# Whastbee-display3.net
KiCad netlist of a schematic drawn in EAGLE
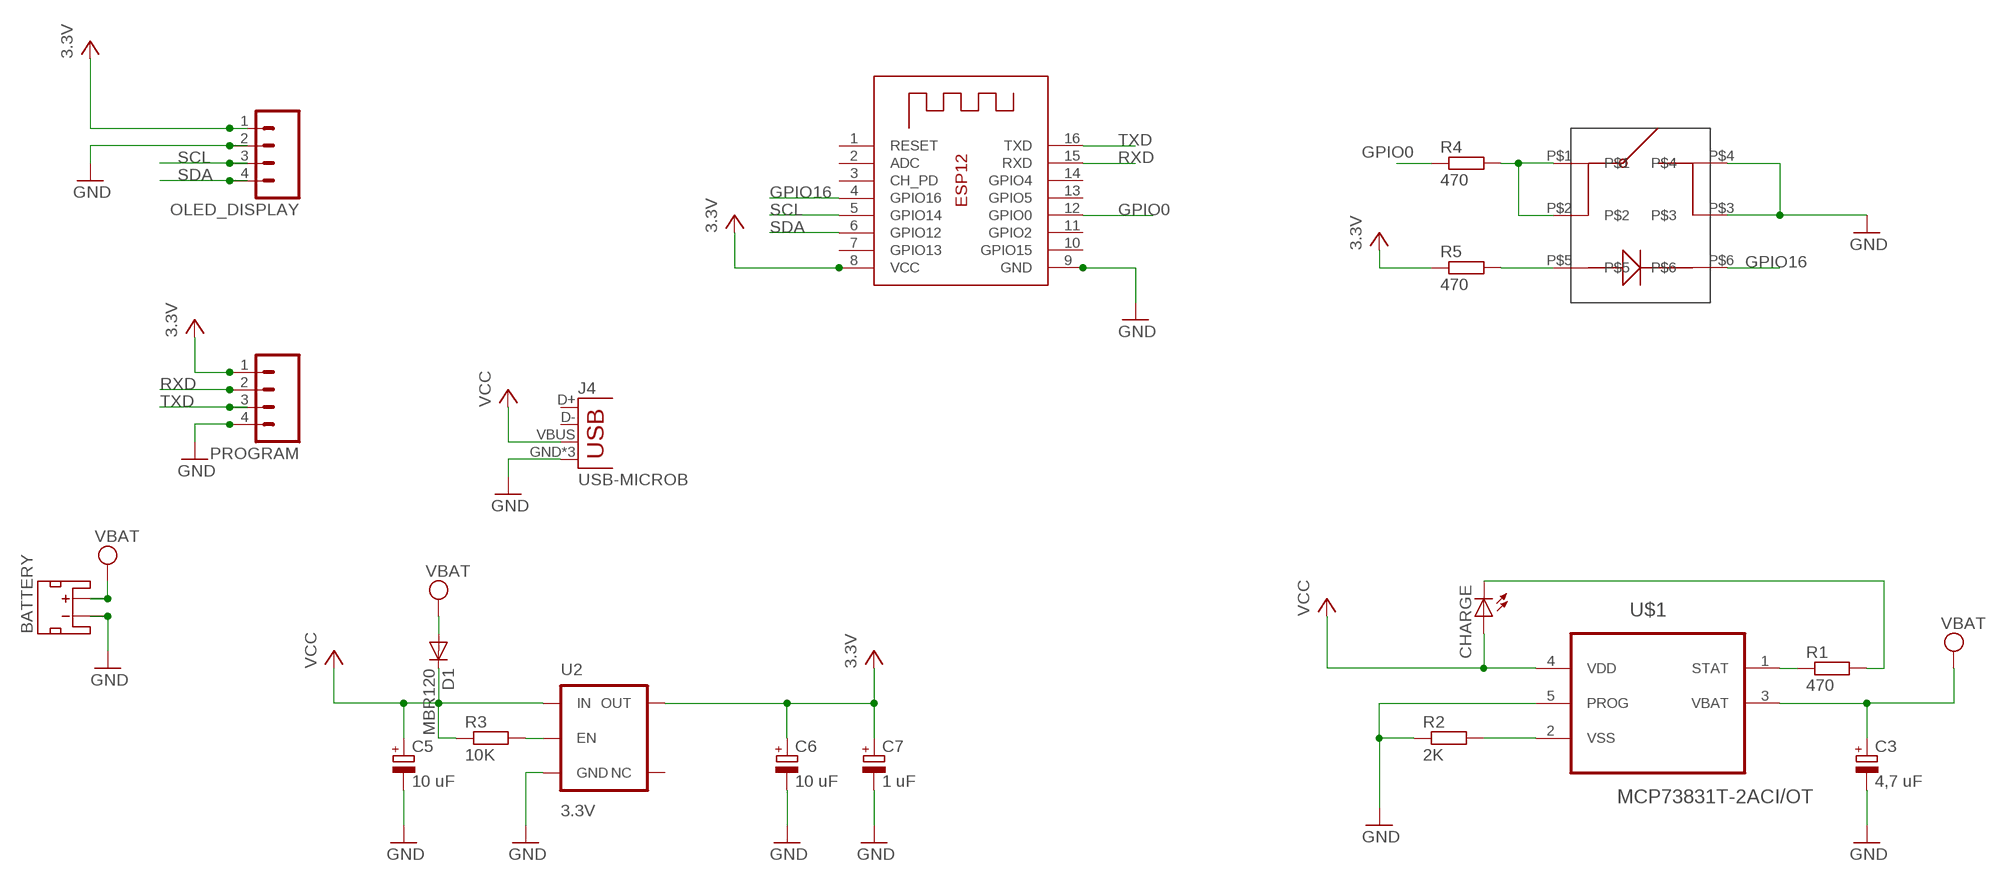
[diagram p0: schematic, sheet 1]

(export (version "E")
  (design (tool "Eeschema 10.0.6"))
  (components
    (comp (ref "BATTERY")
      (value "JST_2MM_MALE")
      (footprint "eagle-import:JST-2-SMD")
      (libsource (lib "eagle-import") (part "JST_2MM_MALE"))
    )
    (comp (ref "C3")
      (value "4,7 uF")
      (footprint "eagle-import:T_3528-12R")
      (libsource (lib "eagle-import") (part "CPOL-EUT/3528-12R"))
    )
    (comp (ref "C5")
      (value "10 uF")
      (footprint "eagle-import:T_3528-12R")
      (libsource (lib "eagle-import") (part "CPOL-EUT/3528-12R"))
    )
    (comp (ref "C6")
      (value "10 uF")
      (footprint "eagle-import:T_3528-12R")
      (libsource (lib "eagle-import") (part "CPOL-EUT/3528-12R"))
    )
    (comp (ref "C7")
      (value "1 uF")
      (footprint "eagle-import:T_3528-12R")
      (libsource (lib "eagle-import") (part "CPOL-EUT/3528-12R"))
    )
    (comp (ref "CHARGE")
      (value "LEDCHIPLED_0805")
      (footprint "eagle-import:CHIPLED_0805")
      (libsource (lib "eagle-import") (part "LEDCHIPLED_0805"))
    )
    (comp (ref "D1")
      (value "MBR120")
      (footprint "eagle-import:SOD-123_MINI-SMA")
      (libsource (lib "eagle-import") (part "CGRM400-G1"))
    )
    (comp (ref "ESP8266-12")
      (value "ESP-12")
      (footprint "eagle-import:ESP-12")
      (libsource (lib "eagle-import") (part "ESP-12"))
    )
    (comp (ref "J4")
      (value "USB-MICROB")
      (footprint "eagle-import:USB-MICROB")
      (libsource (lib "eagle-import") (part "USB-MICROB"))
    )
    (comp (ref "OLED_DISPLAY")
      (value "M04PTH")
      (footprint "eagle-import:1X04")
      (libsource (lib "eagle-import") (part "M04PTH"))
    )
    (comp (ref "PROGRAM")
      (value "M04LOCK")
      (footprint "eagle-import:1X04_LOCK")
      (libsource (lib "eagle-import") (part "M04LOCK"))
    )
    (comp (ref "R1")
      (value "470")
      (footprint "eagle-import:R0805")
      (libsource (lib "eagle-import") (part "R"))
    )
    (comp (ref "R2")
      (value "2K")
      (footprint "eagle-import:R0805")
      (libsource (lib "eagle-import") (part "R"))
    )
    (comp (ref "R3")
      (value "10K")
      (footprint "eagle-import:R0805")
      (libsource (lib "eagle-import") (part "R"))
    )
    (comp (ref "R4")
      (value "470")
      (footprint "eagle-import:R0805")
      (libsource (lib "eagle-import") (part "R"))
    )
    (comp (ref "R5")
      (value "470")
      (footprint "eagle-import:R0805")
      (libsource (lib "eagle-import") (part "R"))
    )
    (comp (ref "U$1")
      (value "MCP73831T-2ACI/OT")
      (footprint "eagle-import:SOT95P280X145-5N")
      (libsource (lib "eagle-import") (part "MCP73831T-2ACI/OT"))
    )
    (comp (ref "U$2")
      (value "SWITCH-LED_AMIDATA")
      (footprint "eagle-import:LED")
      (libsource (lib "eagle-import") (part "SWITCH-LED_AMIDATA"))
    )
    (comp (ref "U2")
      (value "3.3V")
      (footprint "eagle-import:SOT23-5")
      (libsource (lib "eagle-import") (part "V_REG_AP2112K-3.3V"))
    )
  )
  (nets
    (net (code "1") (name "/GPIO0") (class "Default")
      (node (ref "ESP8266-12") (pin "12") (pinfunction "GPIO0_12") (pintype "bidirectional"))
      (node (ref "R4") (pin "1") (pinfunction "1_1") (pintype "passive"))
    )
    (net (code "2") (name "/GPIO16") (class "Default")
      (node (ref "ESP8266-12") (pin "4") (pinfunction "GPIO16_4") (pintype "bidirectional"))
      (node (ref "U$2") (pin "P$6") (pinfunction "P$6_P$6") (pintype "bidirectional"))
    )
    (net (code "3") (name "/RXD") (class "Default")
      (node (ref "ESP8266-12") (pin "15") (pinfunction "RXD_15") (pintype "input"))
      (node (ref "PROGRAM") (pin "2") (pinfunction "2_2") (pintype "passive"))
    )
    (net (code "4") (name "/SCL") (class "Default")
      (node (ref "ESP8266-12") (pin "5") (pinfunction "GPIO14_5") (pintype "bidirectional"))
      (node (ref "OLED_DISPLAY") (pin "3") (pinfunction "3_3") (pintype "passive"))
    )
    (net (code "5") (name "/SDA") (class "Default")
      (node (ref "ESP8266-12") (pin "6") (pinfunction "GPIO12_6") (pintype "bidirectional"))
      (node (ref "OLED_DISPLAY") (pin "4") (pinfunction "4_4") (pintype "passive"))
    )
    (net (code "6") (name "/TXD") (class "Default")
      (node (ref "ESP8266-12") (pin "16") (pinfunction "TXD_16") (pintype "output"))
      (node (ref "PROGRAM") (pin "3") (pinfunction "3_3") (pintype "passive"))
    )
    (net (code "7") (name "3.3V") (class "Default")
      (node (ref "C6") (pin "+") (pinfunction "+_+") (pintype "passive"))
      (node (ref "C7") (pin "+") (pinfunction "+_+") (pintype "passive"))
      (node (ref "ESP8266-12") (pin "8") (pinfunction "VCC_8") (pintype "power_in"))
      (node (ref "OLED_DISPLAY") (pin "1") (pinfunction "1_1") (pintype "passive"))
      (node (ref "PROGRAM") (pin "1") (pinfunction "1_1") (pintype "passive"))
      (node (ref "R5") (pin "1") (pinfunction "1_1") (pintype "passive"))
      (node (ref "U2") (pin "5") (pinfunction "OUT_5") (pintype "passive"))
    )
    (net (code "8") (name "GND") (class "Default")
      (node (ref "BATTERY") (pin "1") (pinfunction "-_1") (pintype "bidirectional"))
      (node (ref "C3") (pin "-") (pinfunction "-_-") (pintype "passive"))
      (node (ref "C5") (pin "-") (pinfunction "-_-") (pintype "passive"))
      (node (ref "C6") (pin "-") (pinfunction "-_-") (pintype "passive"))
      (node (ref "C7") (pin "-") (pinfunction "-_-") (pintype "passive"))
      (node (ref "ESP8266-12") (pin "9") (pinfunction "GND_9") (pintype "power_in"))
      (node (ref "J4") (pin "GND") (pinfunction "GND_GND") (pintype "bidirectional"))
      (node (ref "J4") (pin "MT1") (pinfunction "GND_MT1") (pintype "bidirectional"))
      (node (ref "J4") (pin "MT2") (pinfunction "GND_MT2") (pintype "bidirectional"))
      (node (ref "OLED_DISPLAY") (pin "2") (pinfunction "2_2") (pintype "passive"))
      (node (ref "PROGRAM") (pin "4") (pinfunction "4_4") (pintype "passive"))
      (node (ref "R2") (pin "1") (pinfunction "1_1") (pintype "passive"))
      (node (ref "U$1") (pin "5") (pinfunction "PROG_5") (pintype "input"))
      (node (ref "U$2") (pin "P$3") (pinfunction "P$3_P$3") (pintype "bidirectional"))
      (node (ref "U$2") (pin "P$4") (pinfunction "P$4_P$4") (pintype "bidirectional"))
      (node (ref "U2") (pin "2") (pinfunction "GND_2") (pintype "input"))
    )
    (net (code "9") (name "Net-(CHARGE-PadC)") (class "Default")
      (node (ref "CHARGE") (pin "C") (pinfunction "C_C") (pintype "passive"))
      (node (ref "R1") (pin "2") (pinfunction "2_2") (pintype "passive"))
    )
    (net (code "10") (name "Net-(R4-Pad2)") (class "Default")
      (node (ref "R4") (pin "2") (pinfunction "2_2") (pintype "passive"))
      (node (ref "U$2") (pin "P$1") (pinfunction "P$1_P$1") (pintype "bidirectional"))
      (node (ref "U$2") (pin "P$2") (pinfunction "P$2_P$2") (pintype "bidirectional"))
    )
    (net (code "11") (name "Net-(R5-Pad2)") (class "Default")
      (node (ref "R5") (pin "2") (pinfunction "2_2") (pintype "passive"))
      (node (ref "U$2") (pin "P$5") (pinfunction "P$5_P$5") (pintype "bidirectional"))
    )
    (net (code "12") (name "Net-(U$1-STAT)") (class "Default")
      (node (ref "R1") (pin "1") (pinfunction "1_1") (pintype "passive"))
      (node (ref "U$1") (pin "1") (pinfunction "STAT_1") (pintype "output"))
    )
    (net (code "13") (name "Net-(U$1-VSS)") (class "Default")
      (node (ref "R2") (pin "2") (pinfunction "2_2") (pintype "passive"))
      (node (ref "U$1") (pin "2") (pinfunction "VSS_2") (pintype "power_in"))
    )
    (net (code "14") (name "Net-(U2-EN)") (class "Default")
      (node (ref "R3") (pin "2") (pinfunction "2_2") (pintype "passive"))
      (node (ref "U2") (pin "3") (pinfunction "EN_3") (pintype "input"))
    )
    (net (code "15") (name "VBAT") (class "Default")
      (node (ref "BATTERY") (pin "2") (pinfunction "+_2") (pintype "bidirectional"))
      (node (ref "C3") (pin "+") (pinfunction "+_+") (pintype "passive"))
      (node (ref "D1") (pin "A") (pinfunction "A_A") (pintype "passive"))
      (node (ref "U$1") (pin "3") (pinfunction "VBAT_3") (pintype "output"))
    )
    (net (code "16") (name "VCC") (class "Default")
      (node (ref "C5") (pin "+") (pinfunction "+_+") (pintype "passive"))
      (node (ref "CHARGE") (pin "A") (pinfunction "A_A") (pintype "passive"))
      (node (ref "D1") (pin "C") (pinfunction "C_C") (pintype "passive"))
      (node (ref "J4") (pin "VBUS") (pinfunction "VBUS_VBUS") (pintype "bidirectional"))
      (node (ref "R3") (pin "1") (pinfunction "1_1") (pintype "passive"))
      (node (ref "U$1") (pin "4") (pinfunction "VDD_4") (pintype "power_in"))
      (node (ref "U2") (pin "1") (pinfunction "IN_1") (pintype "input"))
    )
    (net (code "17") (name "unconnected-(BATTERY-PAD1-PadNC1)") (class "Default")
      (node (ref "BATTERY") (pin "NC1") (pinfunction "PAD1_NC1") (pintype "bidirectional"))
    )
    (net (code "18") (name "unconnected-(BATTERY-PAD2-PadNC2)") (class "Default")
      (node (ref "BATTERY") (pin "NC2") (pinfunction "PAD2_NC2") (pintype "bidirectional"))
    )
    (net (code "19") (name "unconnected-(ESP8266-12-ADC-Pad2)") (class "Default")
      (node (ref "ESP8266-12") (pin "2") (pinfunction "ADC_2") (pintype "passive"))
    )
    (net (code "20") (name "unconnected-(ESP8266-12-CH_PD-Pad3)") (class "Default")
      (node (ref "ESP8266-12") (pin "3") (pinfunction "CH_PD_3") (pintype "input"))
    )
    (net (code "21") (name "unconnected-(ESP8266-12-GPIO2-Pad11)") (class "Default")
      (node (ref "ESP8266-12") (pin "11") (pinfunction "GPIO2_11") (pintype "bidirectional"))
    )
    (net (code "22") (name "unconnected-(ESP8266-12-GPIO4-Pad14)") (class "Default")
      (node (ref "ESP8266-12") (pin "14") (pinfunction "GPIO4_14") (pintype "bidirectional"))
    )
    (net (code "23") (name "unconnected-(ESP8266-12-GPIO5-Pad13)") (class "Default")
      (node (ref "ESP8266-12") (pin "13") (pinfunction "GPIO5_13") (pintype "bidirectional"))
    )
    (net (code "24") (name "unconnected-(ESP8266-12-GPIO13-Pad7)") (class "Default")
      (node (ref "ESP8266-12") (pin "7") (pinfunction "GPIO13_7") (pintype "bidirectional"))
    )
    (net (code "25") (name "unconnected-(ESP8266-12-GPIO15-Pad10)") (class "Default")
      (node (ref "ESP8266-12") (pin "10") (pinfunction "GPIO15_10") (pintype "bidirectional"))
    )
    (net (code "26") (name "unconnected-(ESP8266-12-RESET-Pad1)") (class "Default")
      (node (ref "ESP8266-12") (pin "1") (pinfunction "RESET_1") (pintype "input"))
    )
    (net (code "27") (name "unconnected-(J4-PadD+)") (class "Default")
      (node (ref "J4") (pin "D+") (pinfunction "D+_D+") (pintype "bidirectional"))
    )
    (net (code "28") (name "unconnected-(J4-PadD-)") (class "Default")
      (node (ref "J4") (pin "D-") (pinfunction "D-_D-") (pintype "bidirectional"))
    )
    (net (code "29") (name "unconnected-(U2-NC-Pad4)") (class "Default")
      (node (ref "U2") (pin "4") (pinfunction "NC_4") (pintype "input"))
    )
  )
)
